# Alfa_m.net
KiCad netlist of a schematic drawn in EAGLE
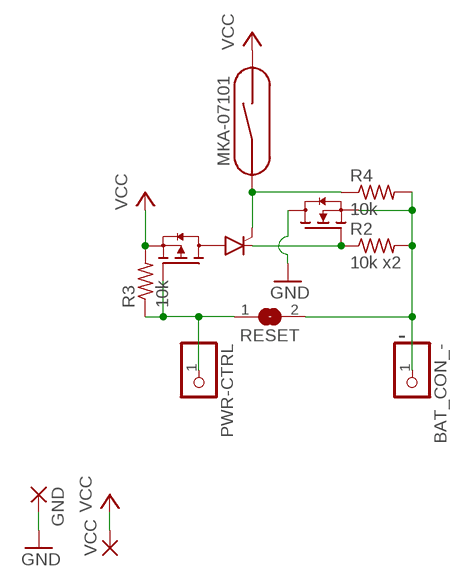
[diagram p0: schematic, sheet 1]

(export (version "E")
  (design (tool "Eeschema 10.0.6"))
  (components
    (comp (ref "AO3407")
      (value "AO3407A")
      (footprint "eagle-import:SOT23-3")
      (libsource (lib "eagle-import") (part "AO3407A"))
    )
    (comp (ref "BAT_CON_-")
      (value "PINHD-1X1")
      (footprint "eagle-import:1X01")
      (libsource (lib "eagle-import") (part "PINHD-1X1"))
    )
    (comp (ref "GND")
      (value "SMD2")
      (footprint "eagle-import:SMD1,27-2,54")
      (libsource (lib "eagle-import") (part "SMD2"))
    )
    (comp (ref "P0102BL")
      (value "P0102BL")
      (footprint "eagle-import:SOT23-3")
      (libsource (lib "eagle-import") (part "P0102BL"))
    )
    (comp (ref "PWR-CTRL")
      (value "PINHD-1X1")
      (footprint "eagle-import:1X01")
      (libsource (lib "eagle-import") (part "PINHD-1X1"))
    )
    (comp (ref "R2")
      (value "10k x2")
      (footprint "eagle-import:R0603")
      (libsource (lib "eagle-import") (part "R-US_R0603"))
    )
    (comp (ref "R3")
      (value "10k")
      (footprint "eagle-import:R0603")
      (libsource (lib "eagle-import") (part "R-US_R0603"))
    )
    (comp (ref "R4")
      (value "10k")
      (footprint "eagle-import:R0603")
      (libsource (lib "eagle-import") (part "R-US_R0603"))
    )
    (comp (ref "RESET")
      (value "SJ")
      (footprint "eagle-import:SJ")
      (libsource (lib "eagle-import") (part "SJ"))
    )
    (comp (ref "SI2302")
      (value "SI2302CDS")
      (footprint "eagle-import:SOT23-3")
      (libsource (lib "eagle-import") (part "SI2302CDS"))
    )
    (comp (ref "VCC")
      (value "SMD2")
      (footprint "eagle-import:SMD1,27-2,54")
      (libsource (lib "eagle-import") (part "SMD2"))
    )
    (comp (ref "МКА-07101")
      (value "МКА-07101")
      (footprint "eagle-import:МКА-07101")
      (libsource (lib "eagle-import") (part "МКА-07101"))
    )
  )
  (nets
    (net (code "1") (name "GND") (class "Default")
      (node (ref "GND") (pin "1") (pinfunction "P_1") (pintype "passive"))
      (node (ref "SI2302") (pin "3") (pinfunction "D_3") (pintype "passive"))
    )
    (net (code "2") (name "Net-(AO3407-D)") (class "Default")
      (node (ref "AO3407") (pin "3") (pinfunction "D_3") (pintype "passive"))
      (node (ref "P0102BL") (pin "3") (pinfunction "A_3") (pintype "passive"))
    )
    (net (code "3") (name "Net-(AO3407-G)") (class "Default")
      (node (ref "AO3407") (pin "1") (pinfunction "G_1") (pintype "passive"))
      (node (ref "PWR-CTRL") (pin "1") (pinfunction "1_1") (pintype "passive"))
      (node (ref "R3") (pin "1") (pinfunction "1_1") (pintype "passive"))
      (node (ref "RESET") (pin "1") (pinfunction "1_1") (pintype "passive"))
    )
    (net (code "4") (name "Net-(P0102BL-C)") (class "Default")
      (node (ref "P0102BL") (pin "1") (pinfunction "C_1") (pintype "passive"))
      (node (ref "R2") (pin "1") (pinfunction "1_1") (pintype "passive"))
      (node (ref "SI2302") (pin "1") (pinfunction "G_1") (pintype "passive"))
    )
    (net (code "5") (name "Net-(P0102BL-G)") (class "Default")
      (node (ref "P0102BL") (pin "2") (pinfunction "G_2") (pintype "passive"))
      (node (ref "R4") (pin "1") (pinfunction "1_1") (pintype "passive"))
      (node (ref "МКА-07101") (pin "1") (pinfunction "1_1") (pintype "bidirectional"))
    )
    (net (code "6") (name "Net-(SI2302-S)") (class "Default")
      (node (ref "BAT_CON_-") (pin "1") (pinfunction "1_1") (pintype "passive"))
      (node (ref "R2") (pin "2") (pinfunction "2_2") (pintype "passive"))
      (node (ref "R4") (pin "2") (pinfunction "2_2") (pintype "passive"))
      (node (ref "RESET") (pin "2") (pinfunction "2_2") (pintype "passive"))
      (node (ref "SI2302") (pin "2") (pinfunction "S_2") (pintype "passive"))
    )
    (net (code "7") (name "VCC") (class "Default")
      (node (ref "AO3407") (pin "2") (pinfunction "S_2") (pintype "passive"))
      (node (ref "R3") (pin "2") (pinfunction "2_2") (pintype "passive"))
      (node (ref "VCC") (pin "1") (pinfunction "P_1") (pintype "passive"))
      (node (ref "МКА-07101") (pin "2") (pinfunction "2_2") (pintype "bidirectional"))
    )
  )
)
